# ALU_Logic.net
KiCad netlist of a schematic drawn in Altium Designer
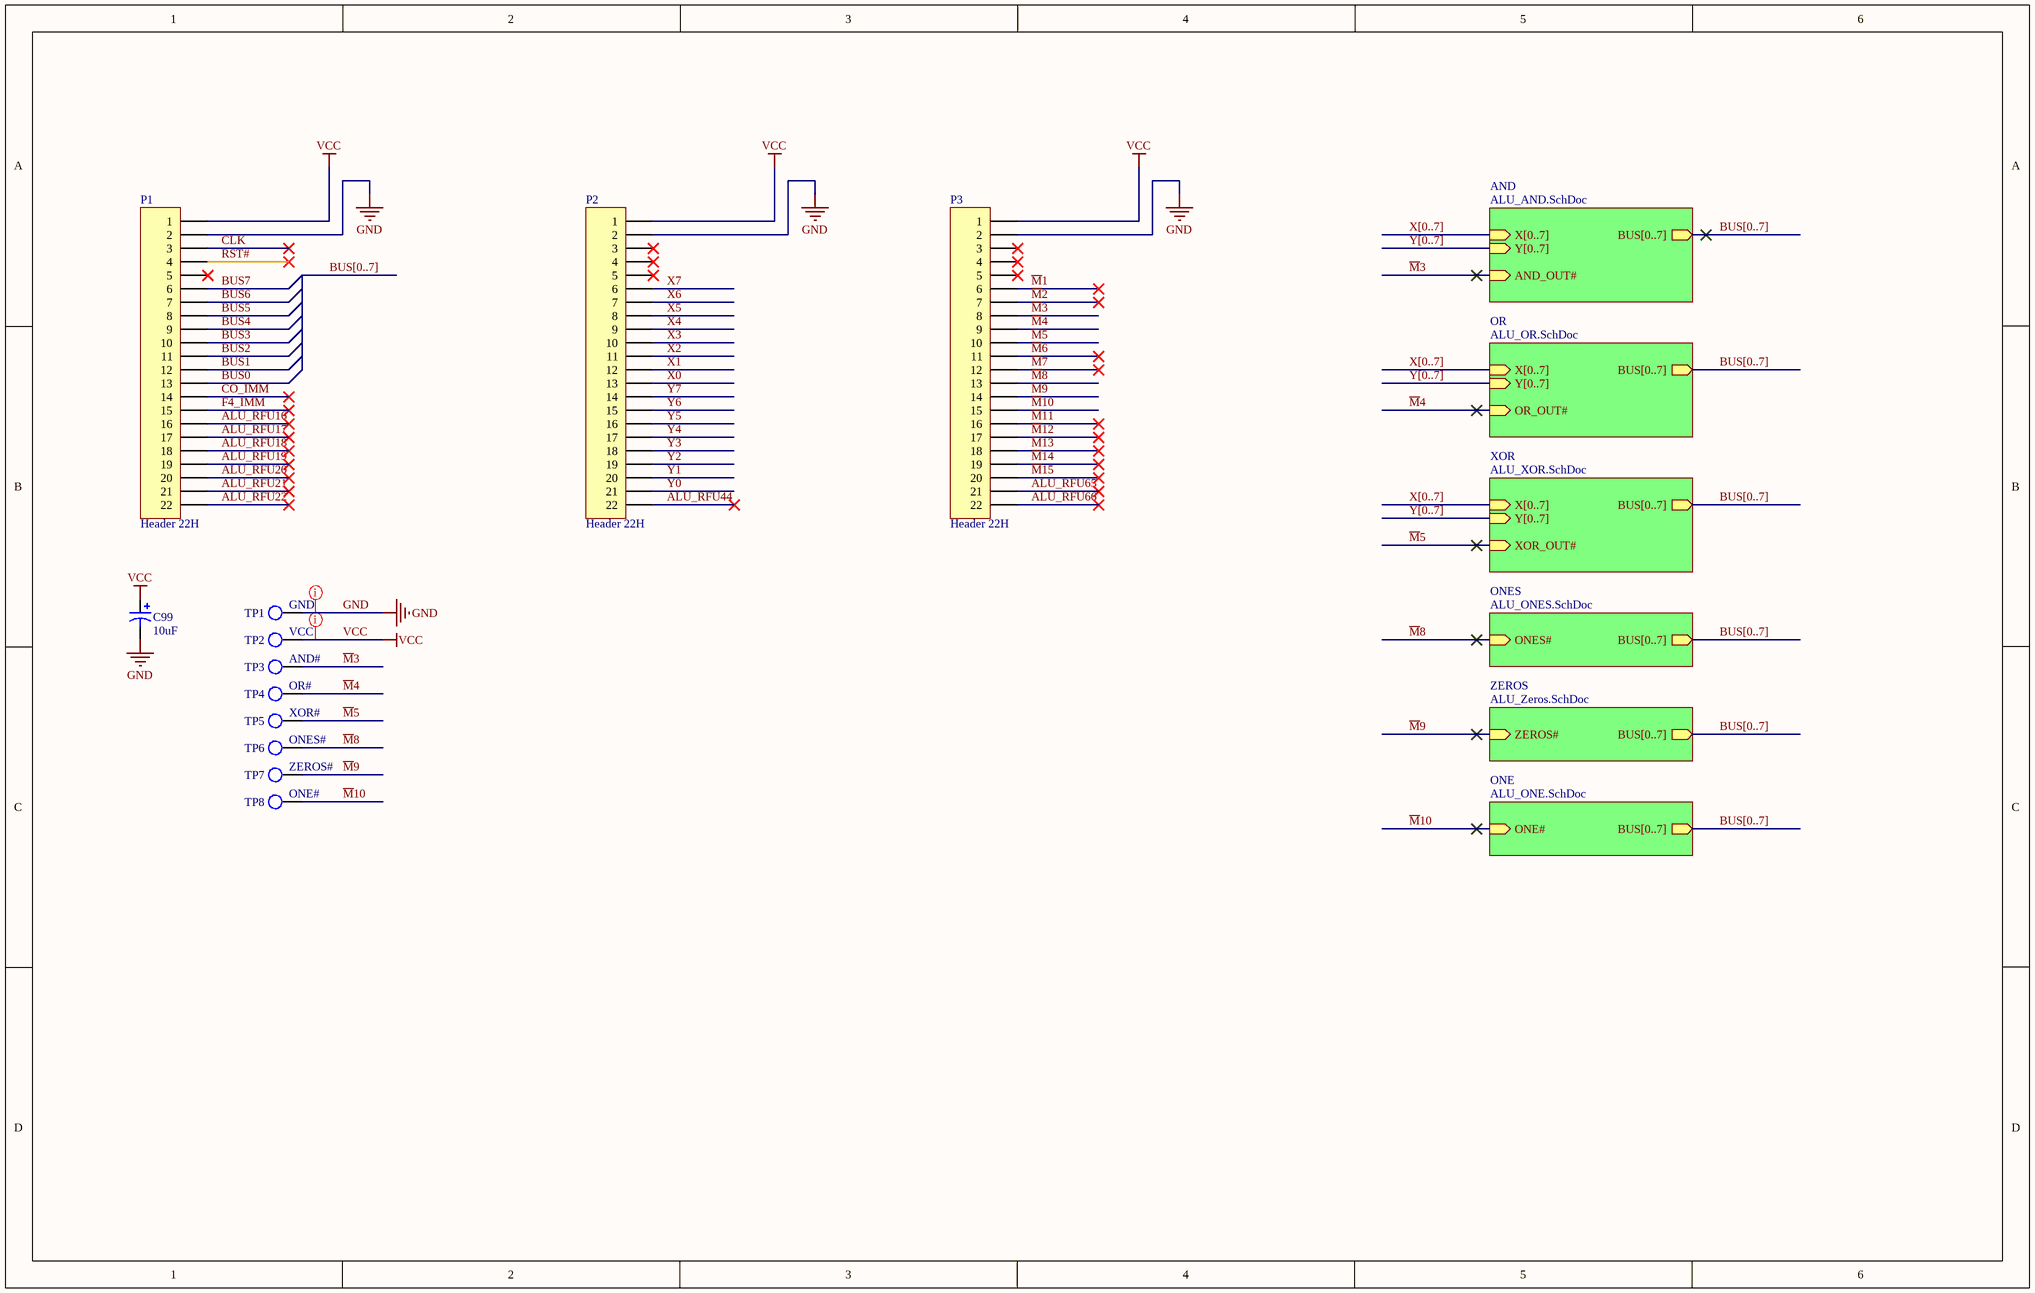
[diagram p0: ALU_Logic.SchDoc]

(export (version "E")
  (design (tool "Eeschema 10.0.6"))
  (components
    (comp (ref "C99")
      (value "10uF")
      (footprint "C5x7")
      (description "Polarized Capacitor")
      (fields (field (name "Comment") "Cap Pol5") (field (name "PUBLISHER") "Altium Limited"))
      (libsource (lib "Miscellaneous Devices") (part "Cap Pol5"))
    )
    (comp (ref "P1")
      (value "Header 22H")
      (footprint "HDR1X22H")
      (description "Header, 22-Pin, Right Angle")
      (fields (field (name "PUBLISHER") "Altium Limited"))
      (libsource (lib "Miscellaneous Connectors") (part "Header 22H"))
    )
    (comp (ref "P2")
      (value "Header 22H")
      (footprint "HDR1X22H")
      (description "Header, 22-Pin, Right Angle")
      (fields (field (name "PUBLISHER") "Altium Limited"))
      (libsource (lib "Miscellaneous Connectors") (part "Header 22H"))
    )
    (comp (ref "P3")
      (value "Header 22H")
      (footprint "HDR1X22H")
      (description "Header, 22-Pin, Right Angle")
      (fields (field (name "PUBLISHER") "Altium Limited"))
      (libsource (lib "Miscellaneous Connectors") (part "Header 22H"))
    )
    (comp (ref "TP1") (value "GND") (footprint "KSTN-5011_V") (libsource (lib "TP") (part "TP")))
    (comp (ref "TP2") (value "VCC") (footprint "KSTN-5011_V") (libsource (lib "TP") (part "TP")))
    (comp (ref "TP3") (value "AND#") (footprint "KSTN-5011_V") (libsource (lib "TP") (part "TP")))
    (comp (ref "TP4") (value "OR#") (footprint "KSTN-5011_V") (libsource (lib "TP") (part "TP")))
    (comp (ref "TP5") (value "XOR#") (footprint "KSTN-5011_V") (libsource (lib "TP") (part "TP")))
    (comp (ref "TP6") (value "ONES#") (footprint "KSTN-5011_V") (libsource (lib "TP") (part "TP")))
    (comp (ref "TP7") (value "ZEROS#") (footprint "KSTN-5011_V") (libsource (lib "TP") (part "TP")))
    (comp (ref "TP8") (value "ONE#") (footprint "KSTN-5011_V") (libsource (lib "TP") (part "TP")))
  )
  (nets
    (net (code "1") (name "/ALU_RFU16") (class "Default")
      (node (ref "P1") (pin "16") (pinfunction "16_16") (pintype "passive+no_connect"))
    )
    (net (code "2") (name "/ALU_RFU17") (class "Default")
      (node (ref "P1") (pin "17") (pinfunction "17_17") (pintype "passive+no_connect"))
    )
    (net (code "3") (name "/ALU_RFU18") (class "Default")
      (node (ref "P1") (pin "18") (pinfunction "18_18") (pintype "passive+no_connect"))
    )
    (net (code "4") (name "/ALU_RFU19") (class "Default")
      (node (ref "P1") (pin "19") (pinfunction "19_19") (pintype "passive+no_connect"))
    )
    (net (code "5") (name "/ALU_RFU20") (class "Default")
      (node (ref "P1") (pin "20") (pinfunction "20_20") (pintype "passive+no_connect"))
    )
    (net (code "6") (name "/ALU_RFU21") (class "Default")
      (node (ref "P1") (pin "21") (pinfunction "21_21") (pintype "passive+no_connect"))
    )
    (net (code "7") (name "/ALU_RFU22") (class "Default")
      (node (ref "P1") (pin "22") (pinfunction "22_22") (pintype "passive+no_connect"))
    )
    (net (code "8") (name "/ALU_RFU44") (class "Default")
      (node (ref "P2") (pin "22") (pinfunction "22_22") (pintype "passive+no_connect"))
    )
    (net (code "9") (name "/ALU_RFU65") (class "Default")
      (node (ref "P3") (pin "21") (pinfunction "21_21") (pintype "passive+no_connect"))
    )
    (net (code "10") (name "/ALU_RFU66") (class "Default")
      (node (ref "P3") (pin "22") (pinfunction "22_22") (pintype "passive+no_connect"))
    )
    (net (code "11") (name "/BUS0") (class "Default")
      (node (ref "P1") (pin "13") (pinfunction "13_13") (pintype "passive"))
    )
    (net (code "12") (name "/BUS1") (class "Default")
      (node (ref "P1") (pin "12") (pinfunction "12_12") (pintype "passive"))
    )
    (net (code "13") (name "/BUS2") (class "Default")
      (node (ref "P1") (pin "11") (pinfunction "11_11") (pintype "passive"))
    )
    (net (code "14") (name "/BUS3") (class "Default")
      (node (ref "P1") (pin "10") (pinfunction "10_10") (pintype "passive"))
    )
    (net (code "15") (name "/BUS4") (class "Default")
      (node (ref "P1") (pin "9") (pinfunction "9_9") (pintype "passive"))
    )
    (net (code "16") (name "/BUS5") (class "Default")
      (node (ref "P1") (pin "8") (pinfunction "8_8") (pintype "passive"))
    )
    (net (code "17") (name "/BUS6") (class "Default")
      (node (ref "P1") (pin "7") (pinfunction "7_7") (pintype "passive"))
    )
    (net (code "18") (name "/BUS7") (class "Default")
      (node (ref "P1") (pin "6") (pinfunction "6_6") (pintype "passive"))
    )
    (net (code "20") (name "/CLK") (class "Default")
      (node (ref "P1") (pin "3") (pinfunction "3_3") (pintype "passive+no_connect"))
    )
    (net (code "21") (name "/CO_IMM") (class "Default")
      (node (ref "P1") (pin "14") (pinfunction "14_14") (pintype "passive+no_connect"))
    )
    (net (code "22") (name "/F4_IMM") (class "Default")
      (node (ref "P1") (pin "15") (pinfunction "15_15") (pintype "passive+no_connect"))
    )
    (net (code "23") (name "/RST#") (class "Default")
      (node (ref "P1") (pin "4") (pinfunction "4_4") (pintype "passive+no_connect"))
    )
    (net (code "24") (name "/X0") (class "Default")
      (node (ref "P2") (pin "13") (pinfunction "13_13") (pintype "passive"))
    )
    (net (code "25") (name "/X1") (class "Default")
      (node (ref "P2") (pin "12") (pinfunction "12_12") (pintype "passive"))
    )
    (net (code "26") (name "/X2") (class "Default")
      (node (ref "P2") (pin "11") (pinfunction "11_11") (pintype "passive"))
    )
    (net (code "27") (name "/X3") (class "Default")
      (node (ref "P2") (pin "10") (pinfunction "10_10") (pintype "passive"))
    )
    (net (code "28") (name "/X4") (class "Default")
      (node (ref "P2") (pin "9") (pinfunction "9_9") (pintype "passive"))
    )
    (net (code "29") (name "/X5") (class "Default")
      (node (ref "P2") (pin "8") (pinfunction "8_8") (pintype "passive"))
    )
    (net (code "30") (name "/X6") (class "Default")
      (node (ref "P2") (pin "7") (pinfunction "7_7") (pintype "passive"))
    )
    (net (code "31") (name "/X7") (class "Default")
      (node (ref "P2") (pin "6") (pinfunction "6_6") (pintype "passive"))
    )
    (net (code "33") (name "/Y0") (class "Default")
      (node (ref "P2") (pin "21") (pinfunction "21_21") (pintype "passive"))
    )
    (net (code "34") (name "/Y1") (class "Default")
      (node (ref "P2") (pin "20") (pinfunction "20_20") (pintype "passive"))
    )
    (net (code "35") (name "/Y2") (class "Default")
      (node (ref "P2") (pin "19") (pinfunction "19_19") (pintype "passive"))
    )
    (net (code "36") (name "/Y3") (class "Default")
      (node (ref "P2") (pin "18") (pinfunction "18_18") (pintype "passive"))
    )
    (net (code "37") (name "/Y4") (class "Default")
      (node (ref "P2") (pin "17") (pinfunction "17_17") (pintype "passive"))
    )
    (net (code "38") (name "/Y5") (class "Default")
      (node (ref "P2") (pin "16") (pinfunction "16_16") (pintype "passive"))
    )
    (net (code "39") (name "/Y6") (class "Default")
      (node (ref "P2") (pin "15") (pinfunction "15_15") (pintype "passive"))
    )
    (net (code "40") (name "/Y7") (class "Default")
      (node (ref "P2") (pin "14") (pinfunction "14_14") (pintype "passive"))
    )
    (net (code "42") (name "/~{M}1") (class "Default")
      (node (ref "P3") (pin "6") (pinfunction "6_6") (pintype "passive+no_connect"))
    )
    (net (code "43") (name "/~{M}2") (class "Default")
      (node (ref "P3") (pin "7") (pinfunction "7_7") (pintype "passive+no_connect"))
    )
    (net (code "44") (name "/~{M}3") (class "Default")
      (node (ref "P3") (pin "8") (pinfunction "8_8") (pintype "passive"))
      (node (ref "TP3") (pin "1") (pintype "passive"))
    )
    (net (code "45") (name "/~{M}4") (class "Default")
      (node (ref "P3") (pin "9") (pinfunction "9_9") (pintype "passive"))
      (node (ref "TP4") (pin "1") (pintype "passive"))
    )
    (net (code "46") (name "/~{M}5") (class "Default")
      (node (ref "P3") (pin "10") (pinfunction "10_10") (pintype "passive"))
      (node (ref "TP5") (pin "1") (pintype "passive"))
    )
    (net (code "47") (name "/~{M}6") (class "Default")
      (node (ref "P3") (pin "11") (pinfunction "11_11") (pintype "passive+no_connect"))
    )
    (net (code "48") (name "/~{M}7") (class "Default")
      (node (ref "P3") (pin "12") (pinfunction "12_12") (pintype "passive+no_connect"))
    )
    (net (code "49") (name "/~{M}8") (class "Default")
      (node (ref "P3") (pin "13") (pinfunction "13_13") (pintype "passive"))
      (node (ref "TP6") (pin "1") (pintype "passive"))
    )
    (net (code "50") (name "/~{M}9") (class "Default")
      (node (ref "P3") (pin "14") (pinfunction "14_14") (pintype "passive"))
      (node (ref "TP7") (pin "1") (pintype "passive"))
    )
    (net (code "51") (name "/~{M}10") (class "Default")
      (node (ref "P3") (pin "15") (pinfunction "15_15") (pintype "passive"))
      (node (ref "TP8") (pin "1") (pintype "passive"))
    )
    (net (code "52") (name "/~{M}11") (class "Default")
      (node (ref "P3") (pin "16") (pinfunction "16_16") (pintype "passive+no_connect"))
    )
    (net (code "53") (name "/~{M}12") (class "Default")
      (node (ref "P3") (pin "17") (pinfunction "17_17") (pintype "passive+no_connect"))
    )
    (net (code "54") (name "/~{M}13") (class "Default")
      (node (ref "P3") (pin "18") (pinfunction "18_18") (pintype "passive+no_connect"))
    )
    (net (code "55") (name "/~{M}14") (class "Default")
      (node (ref "P3") (pin "19") (pinfunction "19_19") (pintype "passive+no_connect"))
    )
    (net (code "56") (name "/~{M}15") (class "Default")
      (node (ref "P3") (pin "20") (pinfunction "20_20") (pintype "passive+no_connect"))
    )
    (net (code "57") (name "GND") (class "Default")
      (node (ref "C99") (pin "2") (pinfunction "2_2") (pintype "passive"))
      (node (ref "P1") (pin "2") (pinfunction "2_2") (pintype "passive"))
      (node (ref "P2") (pin "2") (pinfunction "2_2") (pintype "passive"))
      (node (ref "P3") (pin "2") (pinfunction "2_2") (pintype "passive"))
      (node (ref "TP1") (pin "1") (pintype "passive"))
    )
    (net (code "58") (name "VCC") (class "Default")
      (node (ref "C99") (pin "1") (pinfunction "1_1") (pintype "passive"))
      (node (ref "P1") (pin "1") (pinfunction "1_1") (pintype "passive"))
      (node (ref "P2") (pin "1") (pinfunction "1_1") (pintype "passive"))
      (node (ref "P3") (pin "1") (pinfunction "1_1") (pintype "passive"))
      (node (ref "TP2") (pin "1") (pintype "passive"))
    )
    (net (code "59") (name "unconnected-(P1-Pad5)") (class "Default")
      (node (ref "P1") (pin "5") (pinfunction "5_5") (pintype "passive+no_connect"))
    )
    (net (code "60") (name "unconnected-(P2-Pad3)") (class "Default")
      (node (ref "P2") (pin "3") (pinfunction "3_3") (pintype "passive+no_connect"))
    )
    (net (code "61") (name "unconnected-(P2-Pad4)") (class "Default")
      (node (ref "P2") (pin "4") (pinfunction "4_4") (pintype "passive+no_connect"))
    )
    (net (code "62") (name "unconnected-(P2-Pad5)") (class "Default")
      (node (ref "P2") (pin "5") (pinfunction "5_5") (pintype "passive+no_connect"))
    )
    (net (code "63") (name "unconnected-(P3-Pad3)") (class "Default")
      (node (ref "P3") (pin "3") (pinfunction "3_3") (pintype "passive+no_connect"))
    )
    (net (code "64") (name "unconnected-(P3-Pad4)") (class "Default")
      (node (ref "P3") (pin "4") (pinfunction "4_4") (pintype "passive+no_connect"))
    )
    (net (code "65") (name "unconnected-(P3-Pad5)") (class "Default")
      (node (ref "P3") (pin "5") (pinfunction "5_5") (pintype "passive+no_connect"))
    )
  )
)
